# WR_OSC.net
KiCad netlist of a schematic drawn in Altium Designer
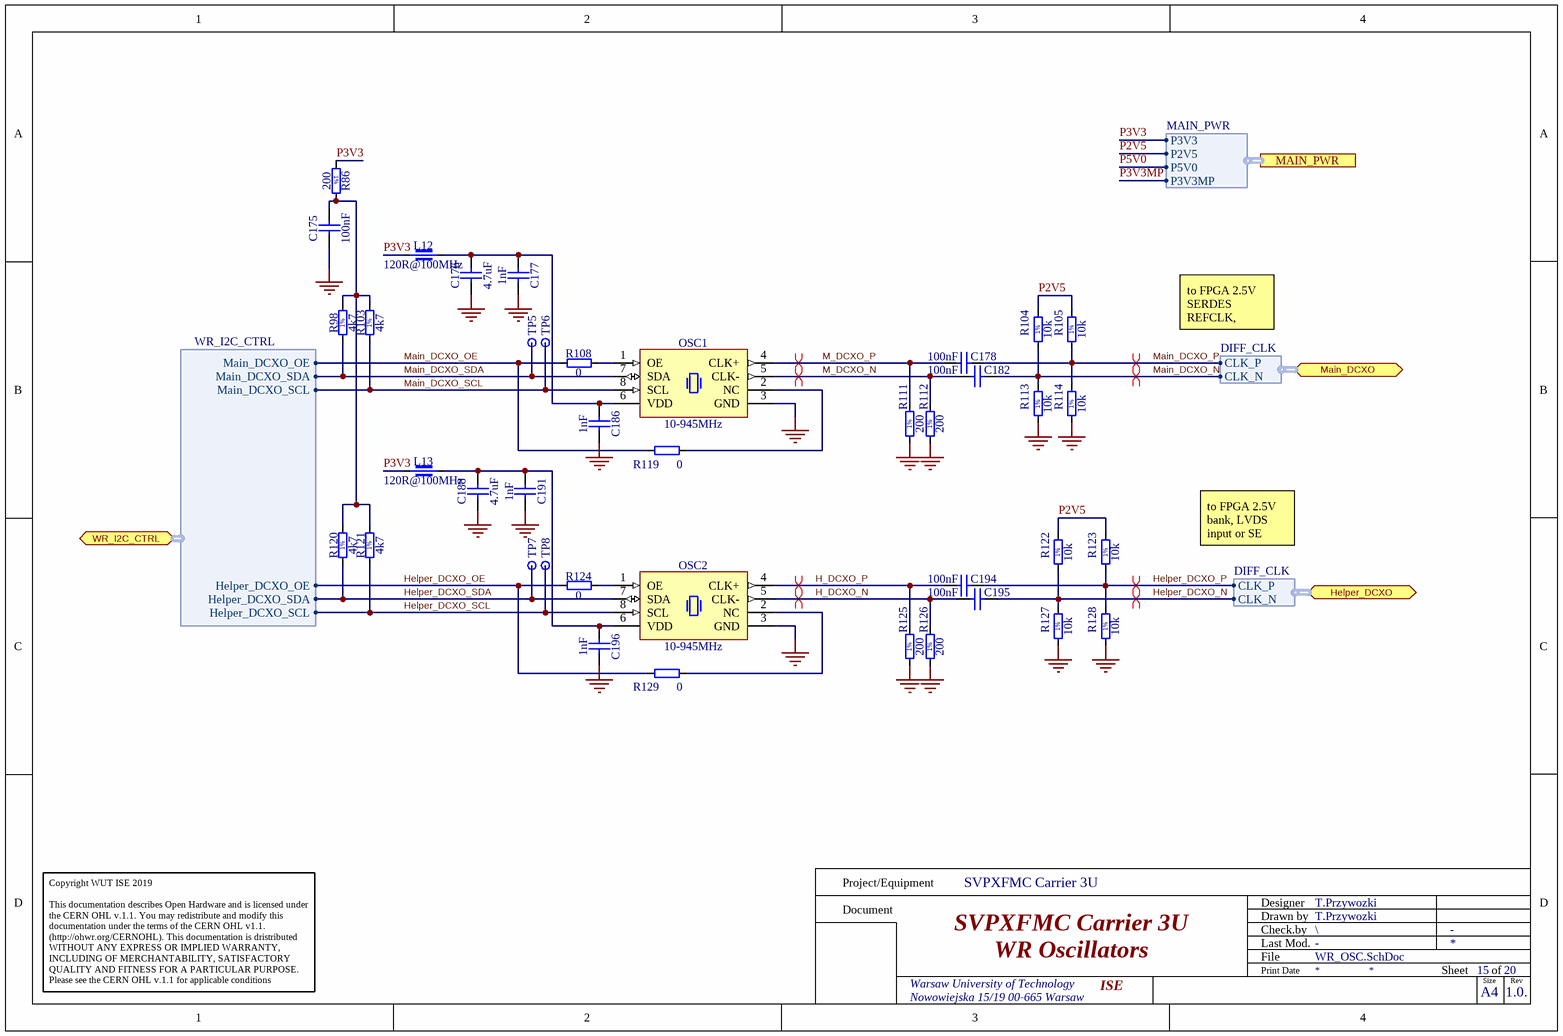
[diagram p0: WR_OSC.SchDoc]

(export (version "E")
  (design (tool "Eeschema 10.0.6"))
  (components
    (comp (ref "C175")
      (value "100nF")
      (footprint "CAPC0603X33N")
      (description "Non-polarised capacitor")
      (fields
        (field (name "MANUFACTURER PART NUMBER") "CC0201_100NF_6.3V_10%_X5R")
        (field (name "MANUFACTURER") "GENERIC")
        (field (name "AUTHOR") "CERN DEM JLC")
      )
      (libsource (lib "Capacitors") (part "Capacitor - non polarized"))
    )
    (comp (ref "C176")
      (value "4.7uF")
      (footprint "CAPC1608X90N")
      (description "Non-polarised capacitor")
      (fields
        (field (name "MANUFACTURER PART NUMBER") "CC0603_4.7UF_25V_10%_X5R")
        (field (name "MANUFACTURER") "GENERIC")
        (field (name "AUTHOR") "CERN DEM JLC")
      )
      (libsource (lib "Capacitors") (part "Capacitor - non polarized"))
    )
    (comp (ref "C177")
      (value "1nF")
      (footprint "CAPC0603X33N")
      (description "Non-polarised capacitor")
      (fields
        (field (name "MANUFACTURER PART NUMBER") "CC0201_1NF_16V_10%_X5R")
        (field (name "MANUFACTURER") "GENERIC")
        (field (name "AUTHOR") "CERN DEM JLC")
      )
      (libsource (lib "Capacitors") (part "Capacitor - non polarized"))
    )
    (comp (ref "C178")
      (value "100nF")
      (footprint "CAPC1005X55N")
      (description "Non-polarised capacitor")
      (fields
        (field (name "MANUFACTURER PART NUMBER") "CC0402_100NF_16V_10%_X5R")
        (field (name "MANUFACTURER") "GENERIC")
        (field (name "AUTHOR") "CERN DEM JLC")
      )
      (libsource (lib "Capacitors") (part "Capacitor - non polarized"))
    )
    (comp (ref "C182")
      (value "100nF")
      (footprint "CAPC1005X55N")
      (description "Non-polarised capacitor")
      (fields
        (field (name "MANUFACTURER PART NUMBER") "CC0402_100NF_16V_10%_X5R")
        (field (name "MANUFACTURER") "GENERIC")
        (field (name "AUTHOR") "CERN DEM JLC")
      )
      (libsource (lib "Capacitors") (part "Capacitor - non polarized"))
    )
    (comp (ref "C186")
      (value "1nF")
      (footprint "CAPC0603X33N")
      (description "Non-polarised capacitor")
      (fields
        (field (name "MANUFACTURER PART NUMBER") "CC0201_1NF_16V_10%_X5R")
        (field (name "MANUFACTURER") "GENERIC")
        (field (name "AUTHOR") "CERN DEM JLC")
      )
      (libsource (lib "Capacitors") (part "Capacitor - non polarized"))
    )
    (comp (ref "C188")
      (value "4.7uF")
      (footprint "CAPC1608X90N")
      (description "Non-polarised capacitor")
      (fields
        (field (name "MANUFACTURER PART NUMBER") "CC0603_4.7UF_25V_10%_X5R")
        (field (name "MANUFACTURER") "GENERIC")
        (field (name "AUTHOR") "CERN DEM JLC")
      )
      (libsource (lib "Capacitors") (part "Capacitor - non polarized"))
    )
    (comp (ref "C191")
      (value "1nF")
      (footprint "CAPC0603X33N")
      (description "Non-polarised capacitor")
      (fields
        (field (name "MANUFACTURER PART NUMBER") "CC0201_1NF_16V_10%_X5R")
        (field (name "MANUFACTURER") "GENERIC")
        (field (name "AUTHOR") "CERN DEM JLC")
      )
      (libsource (lib "Capacitors") (part "Capacitor - non polarized"))
    )
    (comp (ref "C194")
      (value "100nF")
      (footprint "CAPC1005X55N")
      (description "Non-polarised capacitor")
      (fields
        (field (name "MANUFACTURER PART NUMBER") "CC0402_100NF_16V_10%_X5R")
        (field (name "MANUFACTURER") "GENERIC")
        (field (name "AUTHOR") "CERN DEM JLC")
      )
      (libsource (lib "Capacitors") (part "Capacitor - non polarized"))
    )
    (comp (ref "C195")
      (value "100nF")
      (footprint "CAPC1005X55N")
      (description "Non-polarised capacitor")
      (fields
        (field (name "MANUFACTURER PART NUMBER") "CC0402_100NF_16V_10%_X5R")
        (field (name "MANUFACTURER") "GENERIC")
        (field (name "AUTHOR") "CERN DEM JLC")
      )
      (libsource (lib "Capacitors") (part "Capacitor - non polarized"))
    )
    (comp (ref "C196")
      (value "1nF")
      (footprint "CAPC0603X33N")
      (description "Non-polarised capacitor")
      (fields
        (field (name "MANUFACTURER PART NUMBER") "CC0201_1NF_16V_10%_X5R")
        (field (name "MANUFACTURER") "GENERIC")
        (field (name "AUTHOR") "CERN DEM JLC")
      )
      (libsource (lib "Capacitors") (part "Capacitor - non polarized"))
    )
    (comp (ref "L12")
      (value "120R@100MHz")
      (footprint "INDC1608X95N")
      (fields
        (field (name "MANUFACTURER PART NUMBER") "BLM18PG121SN1D")
        (field (name "MANUFACTURER") "MURATA")
        (field (name "PART NUMBER") "IND0603_MURATA_BLM18PG121SN1D")
        (field (name "AUTHOR") "CERN DEM BC")
      )
      (libsource (lib "Inductors & Transformers") (part "Ferrite Bead"))
    )
    (comp (ref "L13")
      (value "120R@100MHz")
      (footprint "INDC1608X95N")
      (fields
        (field (name "MANUFACTURER PART NUMBER") "BLM18PG121SN1D")
        (field (name "MANUFACTURER") "MURATA")
        (field (name "PART NUMBER") "IND0603_MURATA_BLM18PG121SN1D")
        (field (name "AUTHOR") "CERN DEM BC")
      )
      (libsource (lib "Inductors & Transformers") (part "Ferrite Bead"))
    )
    (comp (ref "OSC1")
      (value "10-945MHz")
      (footprint "OSC_SILICON-LAB_SI570")
      (description "Ultra Low Jitter I2C Programmable XO (95 fs), 0.2 to 250MHz")
      (fields
        (field (name "MANUFACTURER") "Silabs")
        (field (name "MANUFACTURER PART NUMBER") "570ACA001527DGR")
      )
      (libsource (lib "TP_LIB") (part "570ACA001527DGR"))
    )
    (comp (ref "OSC2")
      (value "10-945MHz")
      (footprint "OSC_SILICON-LAB_SI570")
      (description "Ultra Low Jitter I2C Programmable XO (95 fs), 0.2 to 250MHz")
      (fields
        (field (name "MANUFACTURER") "Silabs")
        (field (name "MANUFACTURER PART NUMBER") "570ACA001527DGR")
      )
      (libsource (lib "TP_LIB") (part "570ACA001527DGR"))
    )
    (comp (ref "R86")
      (value "200")
      (footprint "RESC1005X40N")
      (description "Resistor - 1%")
      (fields
        (field (name "MANUFACTURER PART NUMBER") "R0402_200R_1%_0.0625W_100PPM")
        (field (name "MANUFACTURER") "GENERIC")
        (field (name "AUTHOR") "CERN DEM JLC")
      )
      (libsource (lib "Resistors") (part "Resistor - 1%"))
    )
    (comp (ref "R98")
      (value "4k7")
      (footprint "RESC1005X40N")
      (description "Resistor - 1%")
      (fields
        (field (name "MANUFACTURER PART NUMBER") "R0402_4K7_1%_0.0625W_100PPM")
        (field (name "MANUFACTURER") "GENERIC")
        (field (name "AUTHOR") "CERN DEM JLC")
      )
      (libsource (lib "Resistors") (part "Resistor - 1%"))
    )
    (comp (ref "R103")
      (value "4k7")
      (footprint "RESC1005X40N")
      (description "Resistor - 1%")
      (fields
        (field (name "MANUFACTURER PART NUMBER") "R0402_4K7_1%_0.0625W_100PPM")
        (field (name "MANUFACTURER") "GENERIC")
        (field (name "AUTHOR") "CERN DEM JLC")
      )
      (libsource (lib "Resistors") (part "Resistor - 1%"))
    )
    (comp (ref "R104")
      (value "10k")
      (footprint "RESC1005X40N")
      (description "Resistor - 1%")
      (fields
        (field (name "MANUFACTURER PART NUMBER") "R0402_10K_1%_0.0625W_100PPM")
        (field (name "MANUFACTURER") "GENERIC")
        (field (name "AUTHOR") "CERN DEM JLC")
      )
      (libsource (lib "Resistors") (part "Resistor - 1%"))
    )
    (comp (ref "R105")
      (value "10k")
      (footprint "RESC1005X40N")
      (description "Resistor - 1%")
      (fields
        (field (name "MANUFACTURER PART NUMBER") "R0402_10K_1%_0.0625W_100PPM")
        (field (name "MANUFACTURER") "GENERIC")
        (field (name "AUTHOR") "CERN DEM JLC")
      )
      (libsource (lib "Resistors") (part "Resistor - 1%"))
    )
    (comp (ref "R108")
      (value "0")
      (footprint "RESC1005X40N")
      (description "Resistor")
      (fields
        (field (name "MANUFACTURER PART NUMBER") "R0402_0R_JUMPER")
        (field (name "MANUFACTURER") "GENERIC")
        (field (name "AUTHOR") "CERN DEM JLC")
      )
      (libsource (lib "Resistors") (part "Resistor"))
    )
    (comp (ref "R111")
      (value "200")
      (footprint "RESC1005X40N")
      (description "Resistor - 1%")
      (fields
        (field (name "MANUFACTURER PART NUMBER") "R0402_200R_1%_0.0625W_100PPM")
        (field (name "MANUFACTURER") "GENERIC")
        (field (name "AUTHOR") "CERN DEM JLC")
      )
      (libsource (lib "Resistors") (part "Resistor - 1%"))
    )
    (comp (ref "R112")
      (value "200")
      (footprint "RESC1005X40N")
      (description "Resistor - 1%")
      (fields
        (field (name "MANUFACTURER PART NUMBER") "R0402_200R_1%_0.0625W_100PPM")
        (field (name "MANUFACTURER") "GENERIC")
        (field (name "AUTHOR") "CERN DEM JLC")
      )
      (libsource (lib "Resistors") (part "Resistor - 1%"))
    )
    (comp (ref "R113")
      (value "10k")
      (footprint "RESC1005X40N")
      (description "Resistor - 1%")
      (fields
        (field (name "MANUFACTURER PART NUMBER") "R0402_10K_1%_0.0625W_100PPM")
        (field (name "MANUFACTURER") "GENERIC")
        (field (name "AUTHOR") "CERN DEM JLC")
      )
      (libsource (lib "Resistors") (part "Resistor - 1%"))
    )
    (comp (ref "R114")
      (value "10k")
      (footprint "RESC1005X40N")
      (description "Resistor - 1%")
      (fields
        (field (name "MANUFACTURER PART NUMBER") "R0402_10K_1%_0.0625W_100PPM")
        (field (name "MANUFACTURER") "GENERIC")
        (field (name "AUTHOR") "CERN DEM JLC")
      )
      (libsource (lib "Resistors") (part "Resistor - 1%"))
    )
    (comp (ref "R119")
      (value "0")
      (footprint "RESC1005X40N")
      (description "Resistor")
      (fields
        (field (name "MANUFACTURER PART NUMBER") "R0402_0R_JUMPER")
        (field (name "MANUFACTURER") "GENERIC")
        (field (name "AUTHOR") "CERN DEM JLC")
      )
      (libsource (lib "Resistors") (part "Resistor"))
    )
    (comp (ref "R120")
      (value "4k7")
      (footprint "RESC1005X40N")
      (description "Resistor - 1%")
      (fields
        (field (name "MANUFACTURER PART NUMBER") "R0402_4K7_1%_0.0625W_100PPM")
        (field (name "MANUFACTURER") "GENERIC")
        (field (name "AUTHOR") "CERN DEM JLC")
      )
      (libsource (lib "Resistors") (part "Resistor - 1%"))
    )
    (comp (ref "R121")
      (value "4k7")
      (footprint "RESC1005X40N")
      (description "Resistor - 1%")
      (fields
        (field (name "MANUFACTURER PART NUMBER") "R0402_4K7_1%_0.0625W_100PPM")
        (field (name "MANUFACTURER") "GENERIC")
        (field (name "AUTHOR") "CERN DEM JLC")
      )
      (libsource (lib "Resistors") (part "Resistor - 1%"))
    )
    (comp (ref "R122")
      (value "10k")
      (footprint "RESC1005X40N")
      (description "Resistor - 1%")
      (fields
        (field (name "MANUFACTURER PART NUMBER") "R0402_10K_1%_0.0625W_100PPM")
        (field (name "MANUFACTURER") "GENERIC")
        (field (name "AUTHOR") "CERN DEM JLC")
      )
      (libsource (lib "Resistors") (part "Resistor - 1%"))
    )
    (comp (ref "R123")
      (value "10k")
      (footprint "RESC1005X40N")
      (description "Resistor - 1%")
      (fields
        (field (name "MANUFACTURER PART NUMBER") "R0402_10K_1%_0.0625W_100PPM")
        (field (name "MANUFACTURER") "GENERIC")
        (field (name "AUTHOR") "CERN DEM JLC")
      )
      (libsource (lib "Resistors") (part "Resistor - 1%"))
    )
    (comp (ref "R124")
      (value "0")
      (footprint "RESC1005X40N")
      (description "Resistor")
      (fields
        (field (name "MANUFACTURER PART NUMBER") "R0402_0R_JUMPER")
        (field (name "MANUFACTURER") "GENERIC")
        (field (name "AUTHOR") "CERN DEM JLC")
      )
      (libsource (lib "Resistors") (part "Resistor"))
    )
    (comp (ref "R125")
      (value "200")
      (footprint "RESC1005X40N")
      (description "Resistor - 1%")
      (fields
        (field (name "MANUFACTURER PART NUMBER") "R0402_200R_1%_0.0625W_100PPM")
        (field (name "MANUFACTURER") "GENERIC")
        (field (name "AUTHOR") "CERN DEM JLC")
      )
      (libsource (lib "Resistors") (part "Resistor - 1%"))
    )
    (comp (ref "R126")
      (value "200")
      (footprint "RESC1005X40N")
      (description "Resistor - 1%")
      (fields
        (field (name "MANUFACTURER PART NUMBER") "R0402_200R_1%_0.0625W_100PPM")
        (field (name "MANUFACTURER") "GENERIC")
        (field (name "AUTHOR") "CERN DEM JLC")
      )
      (libsource (lib "Resistors") (part "Resistor - 1%"))
    )
    (comp (ref "R127")
      (value "10k")
      (footprint "RESC1005X40N")
      (description "Resistor - 1%")
      (fields
        (field (name "MANUFACTURER PART NUMBER") "R0402_10K_1%_0.0625W_100PPM")
        (field (name "MANUFACTURER") "GENERIC")
        (field (name "AUTHOR") "CERN DEM JLC")
      )
      (libsource (lib "Resistors") (part "Resistor - 1%"))
    )
    (comp (ref "R128")
      (value "10k")
      (footprint "RESC1005X40N")
      (description "Resistor - 1%")
      (fields
        (field (name "MANUFACTURER PART NUMBER") "R0402_10K_1%_0.0625W_100PPM")
        (field (name "MANUFACTURER") "GENERIC")
        (field (name "AUTHOR") "CERN DEM JLC")
      )
      (libsource (lib "Resistors") (part "Resistor - 1%"))
    )
    (comp (ref "R129")
      (value "0")
      (footprint "RESC1005X40N")
      (description "Resistor")
      (fields
        (field (name "MANUFACTURER PART NUMBER") "R0402_0R_JUMPER")
        (field (name "MANUFACTURER") "GENERIC")
        (field (name "AUTHOR") "CERN DEM JLC")
      )
      (libsource (lib "Resistors") (part "Resistor"))
    )
    (comp (ref "TP5")
      (value "Test Point")
      (footprint "TPS127")
      (fields (field (name "PART NUMBER") "SMD_PAD_1.27X1.27MM") (field (name "AUTHOR") "CERN DEM JLC"))
      (libsource (lib "Eletro-mechanical") (part "Test Point"))
    )
    (comp (ref "TP6")
      (value "Test Point")
      (footprint "TPS127")
      (fields (field (name "PART NUMBER") "SMD_PAD_1.27X1.27MM") (field (name "AUTHOR") "CERN DEM JLC"))
      (libsource (lib "Eletro-mechanical") (part "Test Point"))
    )
    (comp (ref "TP7")
      (value "Test Point")
      (footprint "TPS127")
      (fields (field (name "PART NUMBER") "SMD_PAD_1.27X1.27MM") (field (name "AUTHOR") "CERN DEM JLC"))
      (libsource (lib "Eletro-mechanical") (part "Test Point"))
    )
    (comp (ref "TP8")
      (value "Test Point")
      (footprint "TPS127")
      (fields (field (name "PART NUMBER") "SMD_PAD_1.27X1.27MM") (field (name "AUTHOR") "CERN DEM JLC"))
      (libsource (lib "Eletro-mechanical") (part "Test Point"))
    )
  )
  (nets
    (net (code "4") (name "/H_DCXO_N") (class "Default")
      (node (ref "C195") (pin "1") (pinfunction "1_1") (pintype "passive"))
      (node (ref "OSC2") (pin "5") (pinfunction "CLK-_5") (pintype "output"))
      (node (ref "R126") (pin "2") (pinfunction "2_2") (pintype "passive"))
    )
    (net (code "5") (name "/H_DCXO_P") (class "Default")
      (node (ref "C194") (pin "1") (pinfunction "1_1") (pintype "passive"))
      (node (ref "OSC2") (pin "4") (pinfunction "CLK+_4") (pintype "output"))
      (node (ref "R125") (pin "2") (pinfunction "2_2") (pintype "passive"))
    )
    (net (code "6") (name "/Helper_DCXO_N") (class "Default")
      (node (ref "C195") (pin "2") (pinfunction "2_2") (pintype "passive"))
      (node (ref "R122") (pin "1") (pinfunction "1_1") (pintype "passive"))
      (node (ref "R127") (pin "2") (pinfunction "2_2") (pintype "passive"))
    )
    (net (code "7") (name "/Helper_DCXO_OE") (class "Default")
      (node (ref "R124") (pin "1") (pinfunction "1_1") (pintype "passive"))
      (node (ref "R129") (pin "1") (pinfunction "1_1") (pintype "passive"))
    )
    (net (code "8") (name "/Helper_DCXO_P") (class "Default")
      (node (ref "C194") (pin "2") (pinfunction "2_2") (pintype "passive"))
      (node (ref "R123") (pin "1") (pinfunction "1_1") (pintype "passive"))
      (node (ref "R128") (pin "2") (pinfunction "2_2") (pintype "passive"))
    )
    (net (code "9") (name "/Helper_DCXO_SCL") (class "Default")
      (node (ref "OSC2") (pin "8") (pinfunction "SCL_8") (pintype "input"))
      (node (ref "R121") (pin "1") (pinfunction "1_1") (pintype "passive"))
      (node (ref "TP8") (pin "1") (pinfunction "1_1") (pintype "bidirectional"))
    )
    (net (code "10") (name "/Helper_DCXO_SDA") (class "Default")
      (node (ref "OSC2") (pin "7") (pinfunction "SDA_7") (pintype "bidirectional"))
      (node (ref "R120") (pin "1") (pinfunction "1_1") (pintype "passive"))
      (node (ref "TP7") (pin "1") (pinfunction "1_1") (pintype "bidirectional"))
    )
    (net (code "11") (name "/M_DCXO_N") (class "Default")
      (node (ref "C182") (pin "1") (pinfunction "1_1") (pintype "passive"))
      (node (ref "OSC1") (pin "5") (pinfunction "CLK-_5") (pintype "output"))
      (node (ref "R112") (pin "2") (pinfunction "2_2") (pintype "passive"))
    )
    (net (code "12") (name "/M_DCXO_P") (class "Default")
      (node (ref "C178") (pin "1") (pinfunction "1_1") (pintype "passive"))
      (node (ref "OSC1") (pin "4") (pinfunction "CLK+_4") (pintype "output"))
      (node (ref "R111") (pin "2") (pinfunction "2_2") (pintype "passive"))
    )
    (net (code "13") (name "/Main_DCXO_N") (class "Default")
      (node (ref "C182") (pin "2") (pinfunction "2_2") (pintype "passive"))
      (node (ref "R104") (pin "1") (pinfunction "1_1") (pintype "passive"))
      (node (ref "R113") (pin "2") (pinfunction "2_2") (pintype "passive"))
    )
    (net (code "14") (name "/Main_DCXO_OE") (class "Default")
      (node (ref "R108") (pin "1") (pinfunction "1_1") (pintype "passive"))
      (node (ref "R119") (pin "1") (pinfunction "1_1") (pintype "passive"))
    )
    (net (code "15") (name "/Main_DCXO_P") (class "Default")
      (node (ref "C178") (pin "2") (pinfunction "2_2") (pintype "passive"))
      (node (ref "R105") (pin "1") (pinfunction "1_1") (pintype "passive"))
      (node (ref "R114") (pin "2") (pinfunction "2_2") (pintype "passive"))
    )
    (net (code "16") (name "/Main_DCXO_SCL") (class "Default")
      (node (ref "OSC1") (pin "8") (pinfunction "SCL_8") (pintype "input"))
      (node (ref "R103") (pin "1") (pinfunction "1_1") (pintype "passive"))
      (node (ref "TP6") (pin "1") (pinfunction "1_1") (pintype "bidirectional"))
    )
    (net (code "17") (name "/Main_DCXO_SDA") (class "Default")
      (node (ref "OSC1") (pin "7") (pinfunction "SDA_7") (pintype "bidirectional"))
      (node (ref "R98") (pin "1") (pinfunction "1_1") (pintype "passive"))
      (node (ref "TP5") (pin "1") (pinfunction "1_1") (pintype "bidirectional"))
    )
    (net (code "18") (name "/P2V5") (class "Default")
      (node (ref "R104") (pin "2") (pinfunction "2_2") (pintype "passive"))
      (node (ref "R105") (pin "2") (pinfunction "2_2") (pintype "passive"))
      (node (ref "R122") (pin "2") (pinfunction "2_2") (pintype "passive"))
      (node (ref "R123") (pin "2") (pinfunction "2_2") (pintype "passive"))
    )
    (net (code "19") (name "/P3V3") (class "Default")
      (node (ref "L12") (pin "1") (pinfunction "1_1") (pintype "passive"))
      (node (ref "L13") (pin "1") (pinfunction "1_1") (pintype "passive"))
      (node (ref "R86") (pin "1") (pinfunction "1_1") (pintype "passive"))
    )
    (net (code "25") (name "GND") (class "Default")
      (node (ref "C175") (pin "1") (pinfunction "1_1") (pintype "passive"))
      (node (ref "C176") (pin "1") (pinfunction "1_1") (pintype "passive"))
      (node (ref "C177") (pin "1") (pinfunction "1_1") (pintype "passive"))
      (node (ref "C186") (pin "1") (pinfunction "1_1") (pintype "passive"))
      (node (ref "C188") (pin "1") (pinfunction "1_1") (pintype "passive"))
      (node (ref "C191") (pin "1") (pinfunction "1_1") (pintype "passive"))
      (node (ref "C196") (pin "1") (pinfunction "1_1") (pintype "passive"))
      (node (ref "OSC1") (pin "3") (pinfunction "GND_3") (pintype "power_in"))
      (node (ref "OSC2") (pin "3") (pinfunction "GND_3") (pintype "power_in"))
      (node (ref "R111") (pin "1") (pinfunction "1_1") (pintype "passive"))
      (node (ref "R112") (pin "1") (pinfunction "1_1") (pintype "passive"))
      (node (ref "R113") (pin "1") (pinfunction "1_1") (pintype "passive"))
      (node (ref "R114") (pin "1") (pinfunction "1_1") (pintype "passive"))
      (node (ref "R125") (pin "1") (pinfunction "1_1") (pintype "passive"))
      (node (ref "R126") (pin "1") (pinfunction "1_1") (pintype "passive"))
      (node (ref "R127") (pin "1") (pinfunction "1_1") (pintype "passive"))
      (node (ref "R128") (pin "1") (pinfunction "1_1") (pintype "passive"))
    )
    (net (code "26") (name "Net-(C175-Pad2)") (class "Default")
      (node (ref "C175") (pin "2") (pinfunction "2_2") (pintype "passive"))
      (node (ref "R103") (pin "2") (pinfunction "2_2") (pintype "passive"))
      (node (ref "R120") (pin "2") (pinfunction "2_2") (pintype "passive"))
      (node (ref "R121") (pin "2") (pinfunction "2_2") (pintype "passive"))
      (node (ref "R86") (pin "2") (pinfunction "2_2") (pintype "passive"))
      (node (ref "R98") (pin "2") (pinfunction "2_2") (pintype "passive"))
    )
    (net (code "27") (name "Net-(OSC1-NC)") (class "Default")
      (node (ref "OSC1") (pin "2") (pinfunction "NC_2") (pintype "passive"))
      (node (ref "R119") (pin "2") (pinfunction "2_2") (pintype "passive"))
    )
    (net (code "28") (name "Net-(OSC1-OE)") (class "Default")
      (node (ref "OSC1") (pin "1") (pinfunction "OE_1") (pintype "input"))
      (node (ref "R108") (pin "2") (pinfunction "2_2") (pintype "passive"))
    )
    (net (code "29") (name "Net-(OSC1-VDD)") (class "Default")
      (node (ref "C176") (pin "2") (pinfunction "2_2") (pintype "passive"))
      (node (ref "C177") (pin "2") (pinfunction "2_2") (pintype "passive"))
      (node (ref "C186") (pin "2") (pinfunction "2_2") (pintype "passive"))
      (node (ref "L12") (pin "2") (pinfunction "2_2") (pintype "passive"))
      (node (ref "OSC1") (pin "6") (pinfunction "VDD_6") (pintype "power_in"))
    )
    (net (code "30") (name "Net-(OSC2-NC)") (class "Default")
      (node (ref "OSC2") (pin "2") (pinfunction "NC_2") (pintype "passive"))
      (node (ref "R129") (pin "2") (pinfunction "2_2") (pintype "passive"))
    )
    (net (code "31") (name "Net-(OSC2-OE)") (class "Default")
      (node (ref "OSC2") (pin "1") (pinfunction "OE_1") (pintype "input"))
      (node (ref "R124") (pin "2") (pinfunction "2_2") (pintype "passive"))
    )
    (net (code "32") (name "Net-(OSC2-VDD)") (class "Default")
      (node (ref "C188") (pin "2") (pinfunction "2_2") (pintype "passive"))
      (node (ref "C191") (pin "2") (pinfunction "2_2") (pintype "passive"))
      (node (ref "C196") (pin "2") (pinfunction "2_2") (pintype "passive"))
      (node (ref "L13") (pin "2") (pinfunction "2_2") (pintype "passive"))
      (node (ref "OSC2") (pin "6") (pinfunction "VDD_6") (pintype "power_in"))
    )
  )
)
